# EEZ_AUX_PS_r4B43.net
KiCad netlist of a schematic drawn in EAGLE
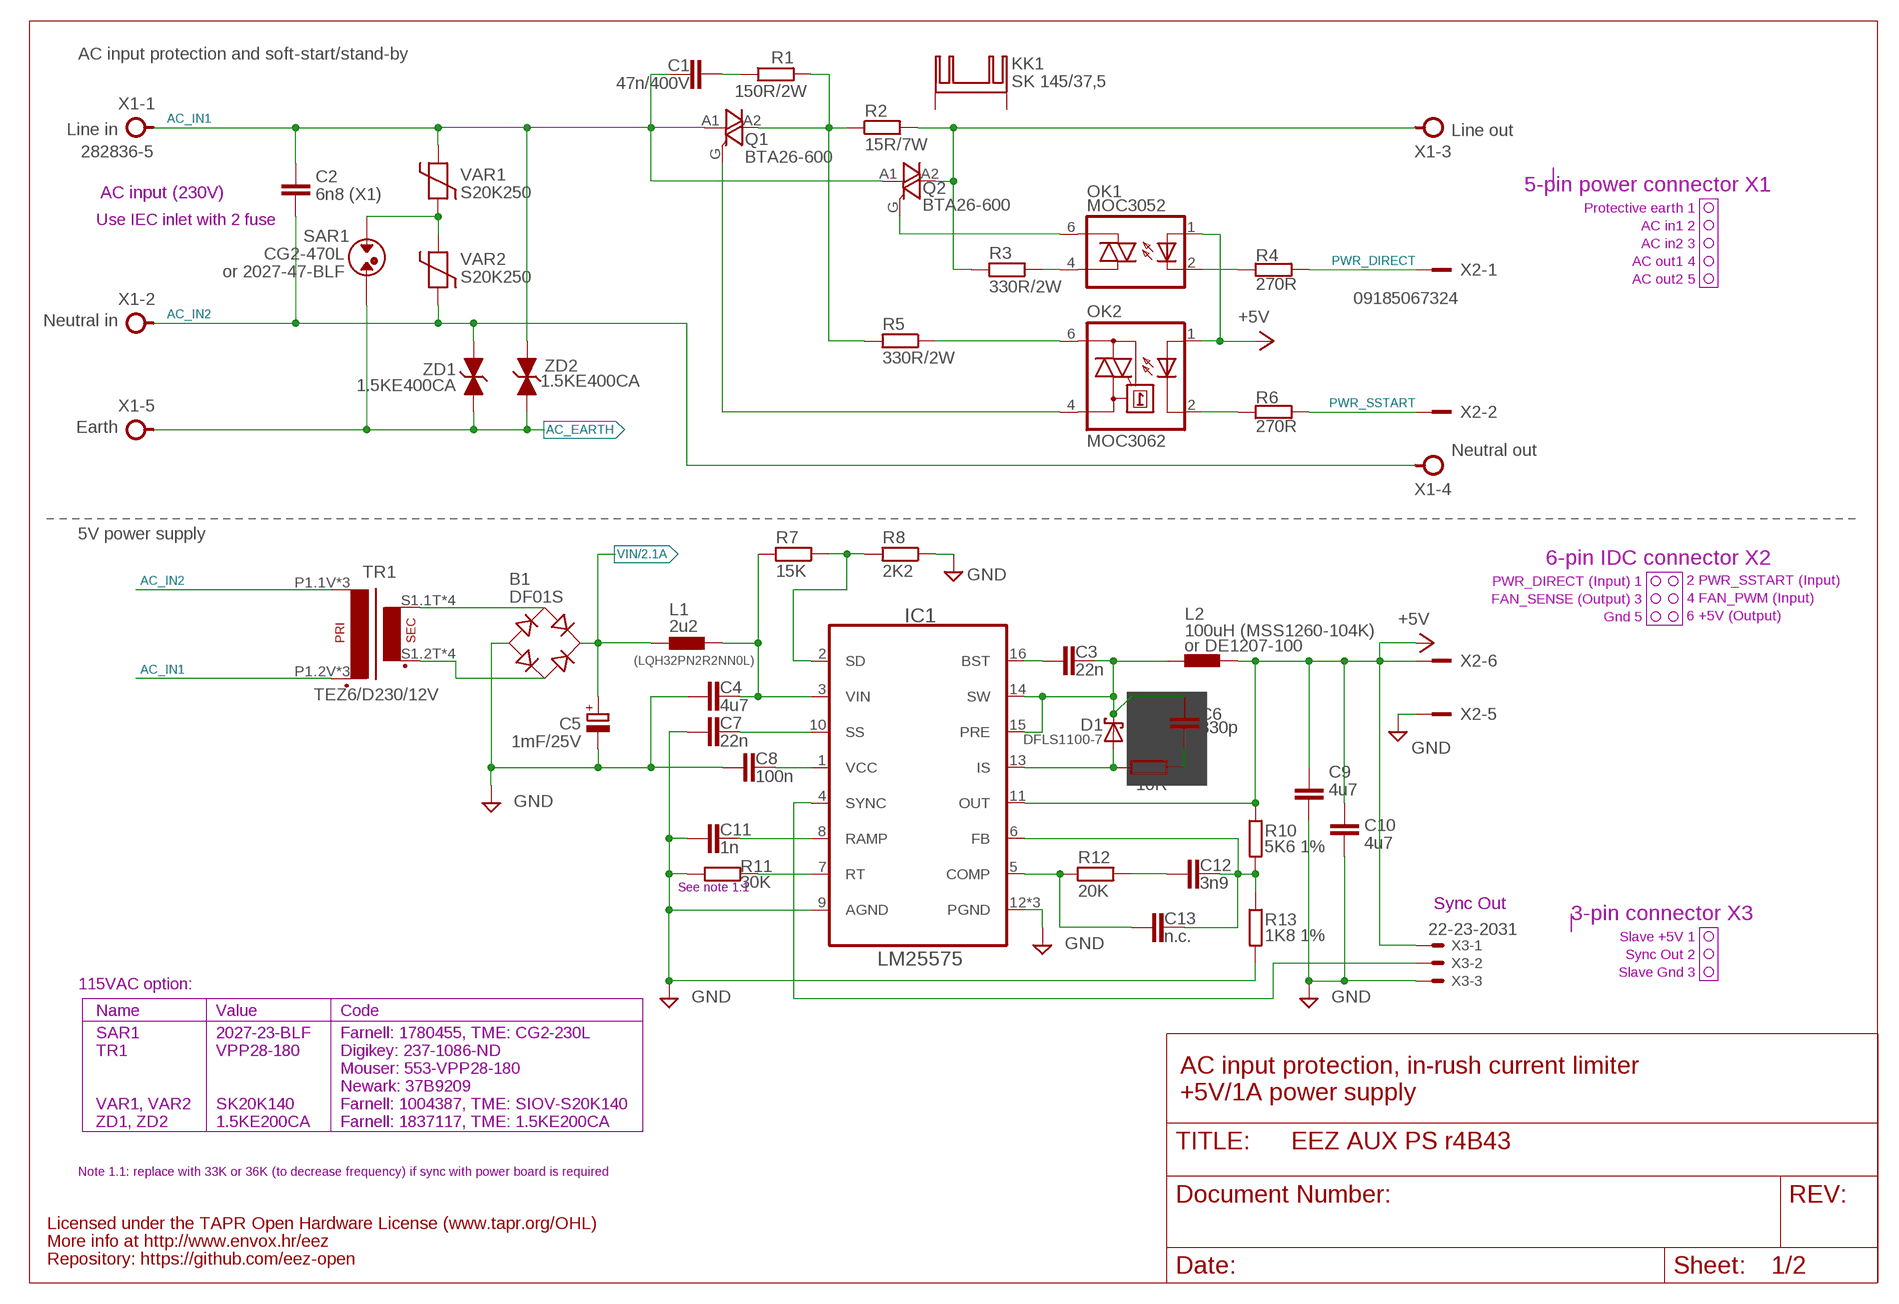
[diagram p0: schematic, sheet 1]
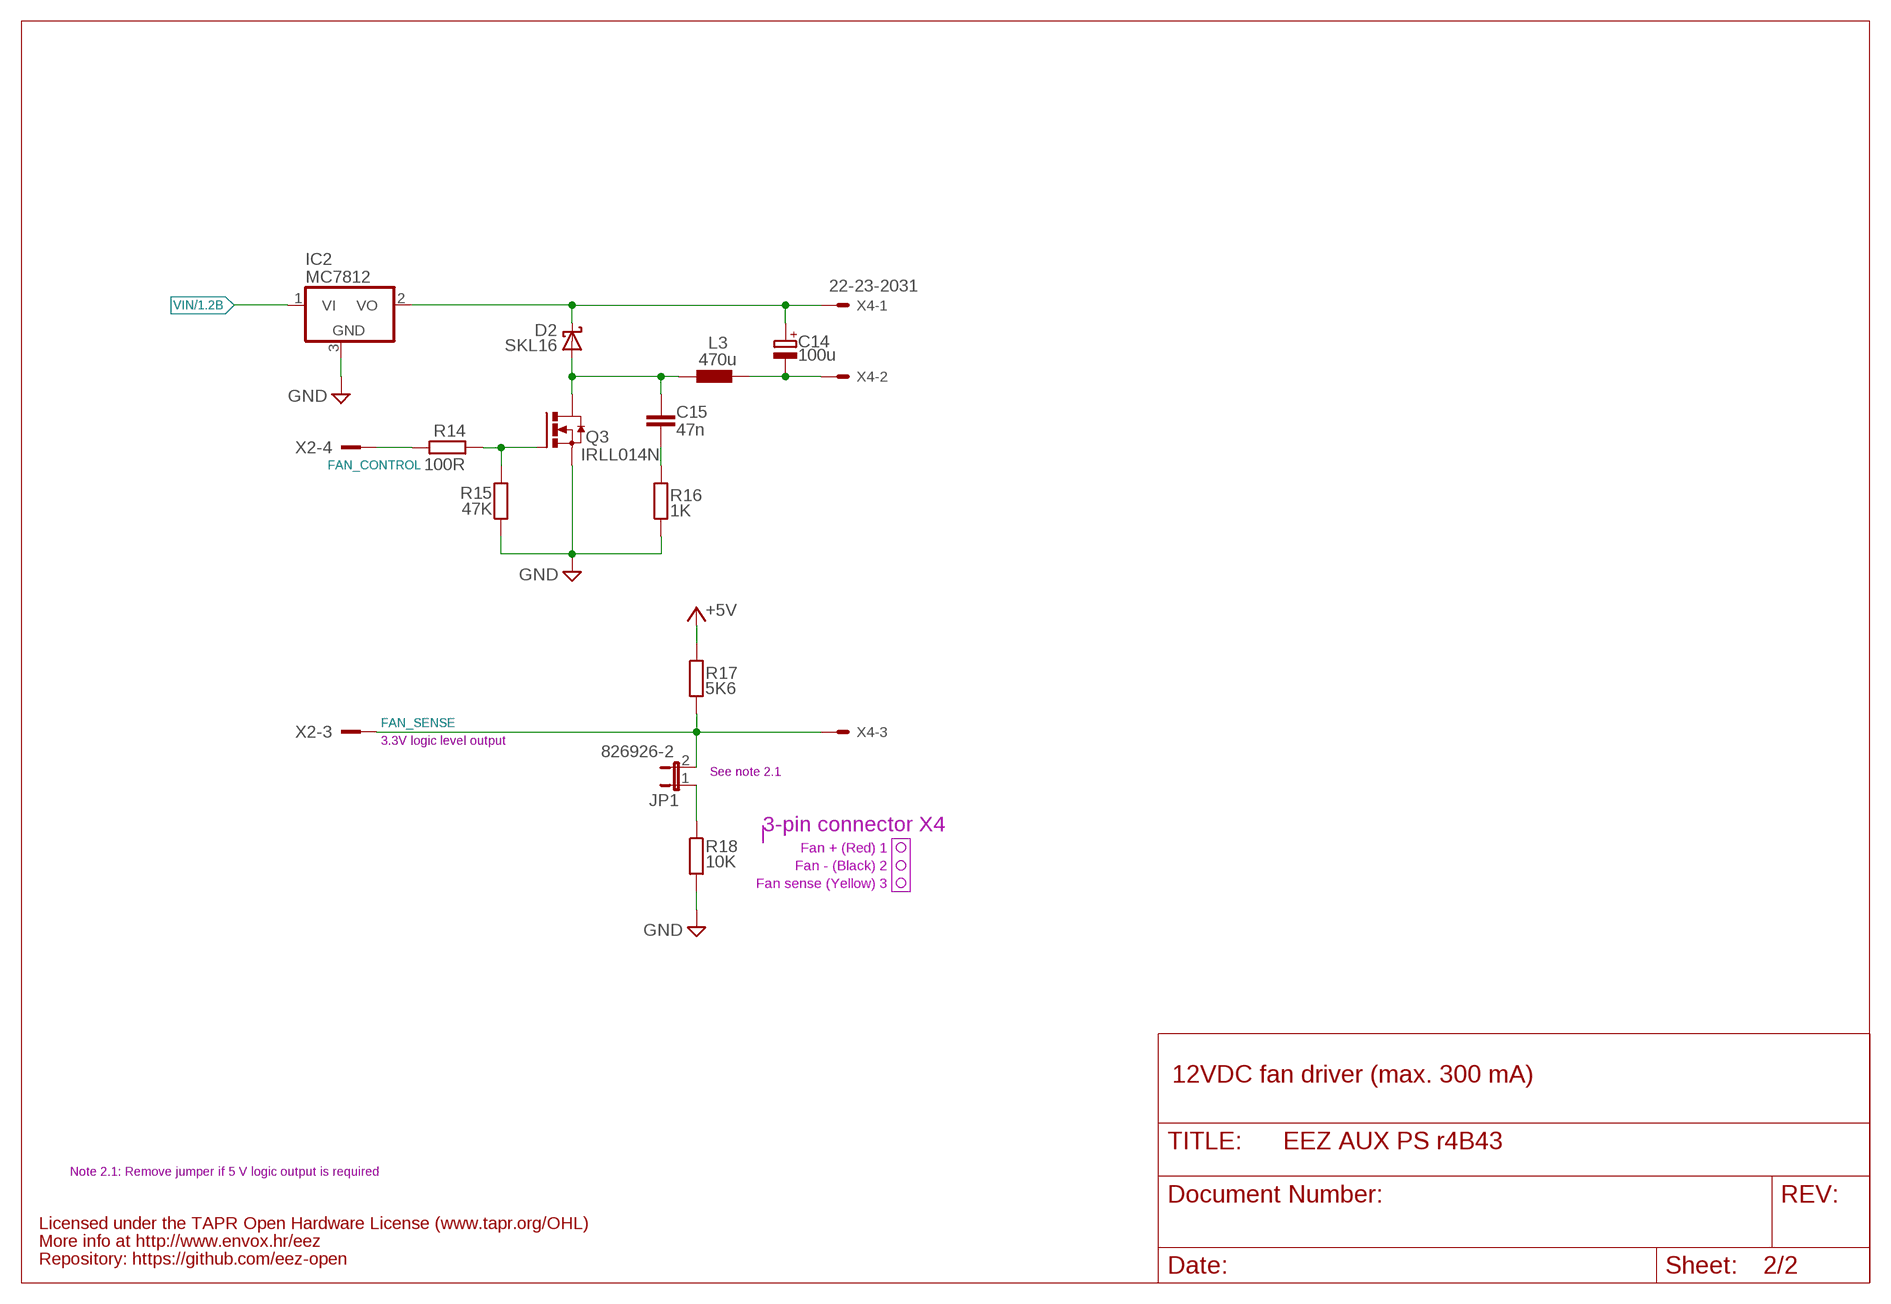
[diagram p1: schematic, sheet 2]

(export (version "E")
  (design (tool "Eeschema 10.0.6"))
  (components
    (comp (ref "B1")
      (value "DF01S")
      (footprint "eagle-import:DFS")
      (libsource (lib "eagle-import") (part "DFS01"))
    )
    (comp (ref "C1")
      (value "47n/400V")
      (footprint "eagle-import:C075-052X106")
      (libsource (lib "eagle-import") (part "C-EU075-052X106"))
    )
    (comp (ref "C2")
      (value "6n8 (X1)")
      (footprint "eagle-import:C102-064X133")
      (libsource (lib "eagle-import") (part "C-EU102-064X133"))
    )
    (comp (ref "C3")
      (value "22n")
      (footprint "eagle-import:C0805")
      (libsource (lib "eagle-import") (part "C-EUC0805"))
    )
    (comp (ref "C4")
      (value "4u7")
      (footprint "eagle-import:C1210")
      (libsource (lib "eagle-import") (part "C-EUC1210"))
    )
    (comp (ref "C5")
      (value "1mF/25V")
      (footprint "eagle-import:ECAP5_10.5")
      (libsource (lib "eagle-import") (part "ECAP5G_10.5MM"))
    )
    (comp (ref "C6")
      (value "330p")
      (footprint "eagle-import:C0805")
      (libsource (lib "eagle-import") (part "C-EUC0805"))
    )
    (comp (ref "C7")
      (value "22n")
      (footprint "eagle-import:C0805")
      (libsource (lib "eagle-import") (part "C-EUC0805"))
    )
    (comp (ref "C8")
      (value "100n")
      (footprint "eagle-import:C0805")
      (libsource (lib "eagle-import") (part "C-EUC0805"))
    )
    (comp (ref "C9")
      (value "4u7")
      (footprint "eagle-import:C1210")
      (libsource (lib "eagle-import") (part "C-EUC1210"))
    )
    (comp (ref "C10")
      (value "4u7")
      (footprint "eagle-import:C1210")
      (libsource (lib "eagle-import") (part "C-EUC1210"))
    )
    (comp (ref "C11")
      (value "1n")
      (footprint "eagle-import:C0805")
      (libsource (lib "eagle-import") (part "C-EUC0805"))
    )
    (comp (ref "C12")
      (value "3n9")
      (footprint "eagle-import:C0805")
      (libsource (lib "eagle-import") (part "C-EUC0805"))
    )
    (comp (ref "C13")
      (value "n.c.")
      (footprint "eagle-import:C0805")
      (libsource (lib "eagle-import") (part "C-EUC0805"))
    )
    (comp (ref "D1")
      (value "DFLS1100-7")
      (footprint "eagle-import:SOD123")
      (libsource (lib "eagle-import") (part "SCHOTTKYSOD123"))
    )
    (comp (ref "IC1")
      (value "LM25575")
      (footprint "eagle-import:SOP65P640X110-17N_HOLE")
      (libsource (lib "eagle-import") (part "LM(2)5575"))
    )
    (comp (ref "KK1")
      (value "SK 145/37,5")
      (footprint "eagle-import:SK145")
      (libsource (lib "eagle-import") (part "SK145"))
    )
    (comp (ref "L1")
      (value "2u2")
      (footprint "eagle-import:L1210")
      (libsource (lib "eagle-import") (part "L1210"))
    )
    (comp (ref "L2")
      (value "100uH (MSS1260-104K)")
      (footprint "eagle-import:MSS1278")
      (libsource (lib "eagle-import") (part "COILCRAFT_MSS1278"))
    )
    (comp (ref "OK1")
      (value "MOC3052")
      (footprint "eagle-import:DIL6-SMD")
      (libsource (lib "eagle-import") (part "MOC305X"))
    )
    (comp (ref "OK2")
      (value "MOC3062")
      (footprint "eagle-import:DIL6-SMD")
      (fields
        (field (name "MF") "FAIRCHILD SEMICONDUCTOR")
        (field (name "MPN") "MOC3033S-M")
        (field (name "MF_1") "FAIRCHILD SEMICONDUCTOR")
        (field (name "MPN_1") "MOC3033S-M")
        (field (name "OC_FARNELL") "unknown")
        (field (name "OC_NEWARK") "05C2878")
      )
      (libsource (lib "eagle-import") (part "MOC30S33"))
    )
    (comp (ref "Q1")
      (value "BTA26-600")
      (footprint "eagle-import:TOP3S-1")
      (libsource (lib "eagle-import") (part "BTA26-V"))
    )
    (comp (ref "Q2")
      (value "BTA26-600")
      (footprint "eagle-import:TOP3S-1")
      (libsource (lib "eagle-import") (part "BTA26-V"))
    )
    (comp (ref "R1")
      (value "150R/2W")
      (footprint "eagle-import:R2512")
      (libsource (lib "eagle-import") (part "R-EU_R2512"))
    )
    (comp (ref "R2")
      (value "15R/7W")
      (footprint "eagle-import:R_0913")
      (libsource (lib "eagle-import") (part "R_EU7W"))
    )
    (comp (ref "R3")
      (value "330R/2W")
      (footprint "eagle-import:R2512")
      (libsource (lib "eagle-import") (part "R-EU_R2512"))
    )
    (comp (ref "R4")
      (value "270R")
      (footprint "eagle-import:R0805")
      (libsource (lib "eagle-import") (part "R-EU_R0805"))
    )
    (comp (ref "R5")
      (value "330R/2W")
      (footprint "eagle-import:R2512")
      (libsource (lib "eagle-import") (part "R-EU_R2512"))
    )
    (comp (ref "R6")
      (value "270R")
      (footprint "eagle-import:R0805")
      (libsource (lib "eagle-import") (part "R-EU_R0805"))
    )
    (comp (ref "R7")
      (value "15K")
      (footprint "eagle-import:R0805")
      (libsource (lib "eagle-import") (part "R-EU_R0805"))
    )
    (comp (ref "R8")
      (value "2K2")
      (footprint "eagle-import:R0805")
      (libsource (lib "eagle-import") (part "R-EU_R0805"))
    )
    (comp (ref "R9")
      (value "10R")
      (footprint "eagle-import:R1206")
      (libsource (lib "eagle-import") (part "R-EU_R1206"))
    )
    (comp (ref "R10")
      (value "5K6 1%")
      (footprint "eagle-import:R0805")
      (libsource (lib "eagle-import") (part "R-EU_R0805"))
    )
    (comp (ref "R11")
      (value "30K")
      (footprint "eagle-import:R0805")
      (libsource (lib "eagle-import") (part "R-EU_R0805"))
    )
    (comp (ref "R12")
      (value "20K")
      (footprint "eagle-import:R0805")
      (libsource (lib "eagle-import") (part "R-EU_R0805"))
    )
    (comp (ref "R13")
      (value "1K8 1%")
      (footprint "eagle-import:R0805")
      (libsource (lib "eagle-import") (part "R-EU_R0805"))
    )
    (comp (ref "SAR1")
      (value "CG2-470L")
      (footprint "eagle-import:SAR")
      (libsource (lib "eagle-import") (part "SAR"))
    )
    (comp (ref "TR1")
      (value "TEZ6/D230/12V")
      (footprint "eagle-import:PCB_TRAFO6VA_TEZ+VPP")
      (libsource (lib "eagle-import") (part "PCB_TRAFO6VA_TEZ+VPP"))
    )
    (comp (ref "VAR1")
      (value "S20K250")
      (footprint "eagle-import:VARISTOR")
      (libsource (lib "eagle-import") (part "VARISTOR"))
    )
    (comp (ref "VAR2")
      (value "S20K250")
      (footprint "eagle-import:VARISTOR")
      (libsource (lib "eagle-import") (part "VARISTOR"))
    )
    (comp (ref "X1")
      (value "282836-5")
      (footprint "eagle-import:TBLOCK5.0_5")
      (libsource (lib "eagle-import") (part "TBLOCK5.0_5A"))
    )
    (comp (ref "X2")
      (value "09185067324")
      (footprint "eagle-import:IDC-6PIN")
      (libsource (lib "eagle-import") (part "IDC-6PIN"))
    )
    (comp (ref "X3")
      (value "22-23-2031")
      (footprint "eagle-import:22-23-2031")
      (fields (field (name "MF") "MOLEX"))
      (libsource (lib "eagle-import") (part "22-23-2031"))
    )
    (comp (ref "ZD1")
      (value "1.5KE400CA")
      (footprint "eagle-import:DO201-BIDIR")
      (libsource (lib "eagle-import") (part "1.5KE-BIDIR"))
    )
    (comp (ref "ZD2")
      (value "1.5KE400CA")
      (footprint "eagle-import:DO201-BIDIR")
      (libsource (lib "eagle-import") (part "1.5KE-BIDIR"))
    )
    (comp (ref "C14")
      (value "100u")
      (footprint "eagle-import:CAPAE660X610N")
      (libsource (lib "eagle-import") (part "ECAPPANASONIC_H"))
    )
    (comp (ref "C15")
      (value "47n")
      (footprint "eagle-import:C0805")
      (libsource (lib "eagle-import") (part "C-EUC0805"))
    )
    (comp (ref "D2")
      (value "SKL16")
      (footprint "eagle-import:SOD123")
      (libsource (lib "eagle-import") (part "SCHOTTKYSOD123"))
    )
    (comp (ref "IC2")
      (value "MC7812")
      (footprint "eagle-import:TO252")
      (libsource (lib "eagle-import") (part "MC78XX"))
    )
    (comp (ref "JP1")
      (value "826926-2")
      (footprint "eagle-import:JP1")
      (libsource (lib "eagle-import") (part "JP1E"))
    )
    (comp (ref "L3")
      (value "470u")
      (footprint "eagle-import:DE0704")
      (libsource (lib "eagle-import") (part "DE0704"))
    )
    (comp (ref "Q3")
      (value "IRLL014N")
      (footprint "eagle-import:SOT223")
      (libsource (lib "eagle-import") (part "N-HEXFET-2D_?-SOT232IRLL014N"))
    )
    (comp (ref "R14")
      (value "100R")
      (footprint "eagle-import:R0805")
      (libsource (lib "eagle-import") (part "R-EU_R0805"))
    )
    (comp (ref "R15")
      (value "47K")
      (footprint "eagle-import:R0805")
      (libsource (lib "eagle-import") (part "R-EU_R0805"))
    )
    (comp (ref "R16")
      (value "1K")
      (footprint "eagle-import:R0805")
      (libsource (lib "eagle-import") (part "R-EU_R0805"))
    )
    (comp (ref "R17")
      (value "5K6")
      (footprint "eagle-import:R0805")
      (libsource (lib "eagle-import") (part "R-EU_R0805"))
    )
    (comp (ref "R18")
      (value "10K")
      (footprint "eagle-import:R0805")
      (libsource (lib "eagle-import") (part "R-EU_R0805"))
    )
    (comp (ref "X4")
      (value "22-23-2031")
      (footprint "eagle-import:22-23-2031")
      (fields (field (name "MF") "MOLEX"))
      (libsource (lib "eagle-import") (part "22-23-2031"))
    )
  )
  (nets
    (net (code "1") (name "+5V") (class "Default")
      (node (ref "C10") (pin "1") (pinfunction "1_1") (pintype "passive"))
      (node (ref "C9") (pin "1") (pinfunction "1_1") (pintype "passive"))
      (node (ref "IC1") (pin "11") (pinfunction "OUT_11") (pintype "output"))
      (node (ref "L2") (pin "2") (pinfunction "2_2") (pintype "passive"))
      (node (ref "OK1") (pin "1") (pinfunction "A_1") (pintype "passive"))
      (node (ref "OK2") (pin "1") (pinfunction "A_1") (pintype "passive"))
      (node (ref "R10") (pin "1") (pinfunction "1_1") (pintype "passive"))
      (node (ref "R17") (pin "1") (pinfunction "1_1") (pintype "passive"))
      (node (ref "X2") (pin "6") (pinfunction "1_6") (pintype "passive"))
      (node (ref "X3") (pin "1") (pinfunction "S_1") (pintype "passive"))
    )
    (net (code "2") (name "AC_EARTH") (class "Default")
      (node (ref "SAR1") (pin "P$2") (pinfunction "P$2_P$2") (pintype "bidirectional"))
      (node (ref "X1") (pin "5") (pinfunction "1_5") (pintype "bidirectional"))
      (node (ref "ZD1") (pin "C") (pinfunction "1_C") (pintype "passive"))
      (node (ref "ZD2") (pin "C") (pinfunction "1_C") (pintype "passive"))
    )
    (net (code "3") (name "AC_IN1") (class "Default")
      (node (ref "C1") (pin "2") (pinfunction "2_2") (pintype "passive"))
      (node (ref "C2") (pin "1") (pinfunction "1_1") (pintype "passive"))
      (node (ref "Q1") (pin "A1") (pinfunction "A1_A1") (pintype "passive"))
      (node (ref "Q2") (pin "A1") (pinfunction "A1_A1") (pintype "passive"))
      (node (ref "TR1") (pin "P1.2V") (pinfunction "P2_P1.2V") (pintype "passive"))
      (node (ref "TR1") (pin "P2.2V") (pinfunction "P2_P2.2V") (pintype "passive"))
      (node (ref "TR1") (pin "P2_TEZ") (pinfunction "P2_P2_TEZ") (pintype "passive"))
      (node (ref "VAR1") (pin "P$2") (pinfunction "P$2_P$2") (pintype "bidirectional"))
      (node (ref "X1") (pin "1") (pinfunction "1_1") (pintype "bidirectional"))
      (node (ref "ZD2") (pin "A") (pinfunction "2_A") (pintype "passive"))
    )
    (net (code "4") (name "AC_IN2") (class "Default")
      (node (ref "C2") (pin "2") (pinfunction "2_2") (pintype "passive"))
      (node (ref "TR1") (pin "P1.1V") (pinfunction "P1_P1.1V") (pintype "passive"))
      (node (ref "TR1") (pin "P1_TEZ") (pinfunction "P1_P1_TEZ") (pintype "passive"))
      (node (ref "TR1") (pin "P2.1V") (pinfunction "P1_P2.1V") (pintype "passive"))
      (node (ref "VAR2") (pin "P$1") (pinfunction "P$1_P$1") (pintype "bidirectional"))
      (node (ref "X1") (pin "2") (pinfunction "1_2") (pintype "bidirectional"))
      (node (ref "X1") (pin "4") (pinfunction "1_4") (pintype "bidirectional"))
      (node (ref "ZD1") (pin "A") (pinfunction "2_A") (pintype "passive"))
    )
    (net (code "5") (name "FAN_CONTROL") (class "Default")
      (node (ref "R14") (pin "2") (pinfunction "2_2") (pintype "passive"))
      (node (ref "X2") (pin "4") (pinfunction "1_4") (pintype "passive"))
    )
    (net (code "6") (name "FAN_SENSE") (class "Default")
      (node (ref "JP1") (pin "2") (pinfunction "2_2") (pintype "passive"))
      (node (ref "R17") (pin "2") (pinfunction "2_2") (pintype "passive"))
      (node (ref "X2") (pin "3") (pinfunction "1_3") (pintype "passive"))
      (node (ref "X4") (pin "3") (pinfunction "S_3") (pintype "passive"))
    )
    (net (code "7") (name "GND") (class "Default")
      (node (ref "B1") (pin "-") (pinfunction "-_-") (pintype "passive"))
      (node (ref "C10") (pin "2") (pinfunction "2_2") (pintype "passive"))
      (node (ref "C11") (pin "1") (pinfunction "1_1") (pintype "passive"))
      (node (ref "C4") (pin "2") (pinfunction "2_2") (pintype "passive"))
      (node (ref "C5") (pin "-") (pinfunction "-_-") (pintype "passive"))
      (node (ref "C7") (pin "2") (pinfunction "2_2") (pintype "passive"))
      (node (ref "C8") (pin "1") (pinfunction "1_1") (pintype "passive"))
      (node (ref "C9") (pin "2") (pinfunction "2_2") (pintype "passive"))
      (node (ref "IC1") (pin "12") (pinfunction "PGND_12") (pintype "passive"))
      (node (ref "IC1") (pin "9") (pinfunction "AGND_9") (pintype "passive"))
      (node (ref "IC1") (pin "TP") (pinfunction "PGND_TP") (pintype "passive"))
      (node (ref "IC1") (pin "TP2") (pinfunction "PGND_TP2") (pintype "passive"))
      (node (ref "IC2") (pin "3") (pinfunction "GND_3") (pintype "passive"))
      (node (ref "Q3") (pin "3") (pinfunction "S_3") (pintype "passive"))
      (node (ref "R11") (pin "2") (pinfunction "2_2") (pintype "passive"))
      (node (ref "R13") (pin "2") (pinfunction "2_2") (pintype "passive"))
      (node (ref "R15") (pin "1") (pinfunction "1_1") (pintype "passive"))
      (node (ref "R16") (pin "1") (pinfunction "1_1") (pintype "passive"))
      (node (ref "R18") (pin "2") (pinfunction "2_2") (pintype "passive"))
      (node (ref "R8") (pin "1") (pinfunction "1_1") (pintype "passive"))
      (node (ref "X2") (pin "5") (pinfunction "1_5") (pintype "passive"))
      (node (ref "X3") (pin "3") (pinfunction "S_3") (pintype "passive"))
    )
    (net (code "8") (name "Net-(B1-PadAC1)") (class "Default")
      (node (ref "B1") (pin "AC1") (pinfunction "AC1_AC1") (pintype "passive"))
      (node (ref "TR1") (pin "S1.1T") (pinfunction "S1_S1.1T") (pintype "passive"))
      (node (ref "TR1") (pin "S1.1V") (pinfunction "S1_S1.1V") (pintype "passive"))
      (node (ref "TR1") (pin "S2.1T") (pinfunction "S1_S2.1T") (pintype "passive"))
      (node (ref "TR1") (pin "S2.1V") (pinfunction "S1_S2.1V") (pintype "passive"))
    )
    (net (code "9") (name "Net-(B1-PadAC2)") (class "Default")
      (node (ref "B1") (pin "AC2") (pinfunction "AC2_AC2") (pintype "passive"))
      (node (ref "TR1") (pin "S1.2T") (pinfunction "S2_S1.2T") (pintype "passive"))
      (node (ref "TR1") (pin "S1.2V") (pinfunction "S2_S1.2V") (pintype "passive"))
      (node (ref "TR1") (pin "S2.2T") (pinfunction "S2_S2.2T") (pintype "passive"))
      (node (ref "TR1") (pin "S2.2V") (pinfunction "S2_S2.2V") (pintype "passive"))
    )
    (net (code "10") (name "Net-(C1-Pad1)") (class "Default")
      (node (ref "C1") (pin "1") (pinfunction "1_1") (pintype "passive"))
      (node (ref "R1") (pin "1") (pinfunction "1_1") (pintype "passive"))
    )
    (net (code "11") (name "Net-(C6-Pad2)") (class "Default")
      (node (ref "C6") (pin "2") (pinfunction "2_2") (pintype "passive"))
      (node (ref "R9") (pin "2") (pinfunction "2_2") (pintype "passive"))
    )
    (net (code "12") (name "Net-(C12-Pad2)") (class "Default")
      (node (ref "C12") (pin "2") (pinfunction "2_2") (pintype "passive"))
      (node (ref "R12") (pin "2") (pinfunction "2_2") (pintype "passive"))
    )
    (net (code "13") (name "Net-(C14-+)") (class "Default")
      (node (ref "C14") (pin "1") (pinfunction "+_1") (pintype "passive"))
      (node (ref "D2") (pin "C") (pinfunction "C_C") (pintype "passive"))
      (node (ref "IC2") (pin "2") (pinfunction "VO_2") (pintype "passive"))
      (node (ref "X4") (pin "1") (pinfunction "S_1") (pintype "passive"))
    )
    (net (code "14") (name "Net-(C14--)") (class "Default")
      (node (ref "C14") (pin "2") (pinfunction "-_2") (pintype "passive"))
      (node (ref "L3") (pin "1") (pinfunction "1_1") (pintype "passive"))
      (node (ref "X4") (pin "2") (pinfunction "S_2") (pintype "passive"))
    )
    (net (code "15") (name "Net-(C15-Pad1)") (class "Default")
      (node (ref "C15") (pin "1") (pinfunction "1_1") (pintype "passive"))
      (node (ref "R16") (pin "2") (pinfunction "2_2") (pintype "passive"))
    )
    (net (code "16") (name "Net-(C15-Pad2)") (class "Default")
      (node (ref "C15") (pin "2") (pinfunction "2_2") (pintype "passive"))
      (node (ref "D2") (pin "A") (pinfunction "A_A") (pintype "passive"))
      (node (ref "L3") (pin "2") (pinfunction "2_2") (pintype "passive"))
      (node (ref "Q3") (pin "2") (pinfunction "D_2") (pintype "passive"))
      (node (ref "Q3") (pin "4") (pinfunction "D_4") (pintype "passive"))
    )
    (net (code "17") (name "Net-(IC1-BST)") (class "Default")
      (node (ref "C3") (pin "2") (pinfunction "2_2") (pintype "passive"))
      (node (ref "IC1") (pin "16") (pinfunction "BST_16") (pintype "input"))
    )
    (net (code "18") (name "Net-(IC1-COMP)") (class "Default")
      (node (ref "C13") (pin "2") (pinfunction "2_2") (pintype "passive"))
      (node (ref "IC1") (pin "5") (pinfunction "COMP_5") (pintype "input"))
      (node (ref "R12") (pin "1") (pinfunction "1_1") (pintype "passive"))
    )
    (net (code "19") (name "Net-(IC1-FB)") (class "Default")
      (node (ref "C12") (pin "1") (pinfunction "1_1") (pintype "passive"))
      (node (ref "C13") (pin "1") (pinfunction "1_1") (pintype "passive"))
      (node (ref "IC1") (pin "6") (pinfunction "FB_6") (pintype "input"))
      (node (ref "R10") (pin "2") (pinfunction "2_2") (pintype "passive"))
      (node (ref "R13") (pin "1") (pinfunction "1_1") (pintype "passive"))
    )
    (net (code "20") (name "Net-(IC1-IS)") (class "Default")
      (node (ref "D1") (pin "A") (pinfunction "A_A") (pintype "passive"))
      (node (ref "IC1") (pin "13") (pinfunction "IS_13") (pintype "input"))
      (node (ref "R9") (pin "1") (pinfunction "1_1") (pintype "passive"))
    )
    (net (code "21") (name "Net-(IC1-PRE)") (class "Default")
      (node (ref "C3") (pin "1") (pinfunction "1_1") (pintype "passive"))
      (node (ref "C6") (pin "1") (pinfunction "1_1") (pintype "passive"))
      (node (ref "D1") (pin "C") (pinfunction "C_C") (pintype "passive"))
      (node (ref "IC1") (pin "14") (pinfunction "SW_14") (pintype "output"))
      (node (ref "IC1") (pin "15") (pinfunction "PRE_15") (pintype "input"))
      (node (ref "L2") (pin "1") (pinfunction "1_1") (pintype "passive"))
    )
    (net (code "22") (name "Net-(IC1-RAMP)") (class "Default")
      (node (ref "C11") (pin "2") (pinfunction "2_2") (pintype "passive"))
      (node (ref "IC1") (pin "8") (pinfunction "RAMP_8") (pintype "input"))
    )
    (net (code "23") (name "Net-(IC1-RT)") (class "Default")
      (node (ref "IC1") (pin "7") (pinfunction "RT_7") (pintype "input"))
      (node (ref "R11") (pin "1") (pinfunction "1_1") (pintype "passive"))
    )
    (net (code "24") (name "Net-(IC1-SD)") (class "Default")
      (node (ref "IC1") (pin "2") (pinfunction "SD_2") (pintype "input"))
      (node (ref "R7") (pin "1") (pinfunction "1_1") (pintype "passive"))
      (node (ref "R8") (pin "2") (pinfunction "2_2") (pintype "passive"))
    )
    (net (code "25") (name "Net-(IC1-SS)") (class "Default")
      (node (ref "C7") (pin "1") (pinfunction "1_1") (pintype "passive"))
      (node (ref "IC1") (pin "10") (pinfunction "SS_10") (pintype "input"))
    )
    (net (code "26") (name "Net-(IC1-SYNC)") (class "Default")
      (node (ref "IC1") (pin "4") (pinfunction "SYNC_4") (pintype "input"))
      (node (ref "X3") (pin "2") (pinfunction "S_2") (pintype "passive"))
    )
    (net (code "27") (name "Net-(IC1-VCC)") (class "Default")
      (node (ref "C8") (pin "2") (pinfunction "2_2") (pintype "passive"))
      (node (ref "IC1") (pin "1") (pinfunction "VCC_1") (pintype "power_in"))
    )
    (net (code "28") (name "Net-(IC1-VIN)") (class "Default")
      (node (ref "C4") (pin "1") (pinfunction "1_1") (pintype "passive"))
      (node (ref "IC1") (pin "3") (pinfunction "VIN_3") (pintype "input"))
      (node (ref "L1") (pin "2") (pinfunction "2_2") (pintype "passive"))
      (node (ref "R7") (pin "2") (pinfunction "2_2") (pintype "passive"))
    )
    (net (code "29") (name "Net-(JP1-Pad1)") (class "Default")
      (node (ref "JP1") (pin "1") (pinfunction "1_1") (pintype "passive"))
      (node (ref "R18") (pin "1") (pinfunction "1_1") (pintype "passive"))
    )
    (net (code "30") (name "Net-(OK1-A1)") (class "Default")
      (node (ref "OK1") (pin "4") (pinfunction "A1_4") (pintype "passive"))
      (node (ref "R3") (pin "1") (pinfunction "1_1") (pintype "passive"))
    )
    (net (code "31") (name "Net-(OK1-A2)") (class "Default")
      (node (ref "OK1") (pin "6") (pinfunction "A2_6") (pintype "passive"))
      (node (ref "Q2") (pin "G") (pinfunction "G_G") (pintype "passive"))
    )
    (net (code "32") (name "Net-(OK1-C)") (class "Default")
      (node (ref "OK1") (pin "2") (pinfunction "C_2") (pintype "passive"))
      (node (ref "R4") (pin "1") (pinfunction "1_1") (pintype "passive"))
    )
    (net (code "33") (name "Net-(OK2-A1)") (class "Default")
      (node (ref "OK2") (pin "4") (pinfunction "A1_4") (pintype "passive"))
      (node (ref "Q1") (pin "G") (pinfunction "G_G") (pintype "passive"))
    )
    (net (code "34") (name "Net-(OK2-A2)") (class "Default")
      (node (ref "OK2") (pin "6") (pinfunction "A2_6") (pintype "passive"))
      (node (ref "R5") (pin "1") (pinfunction "1_1") (pintype "passive"))
    )
    (net (code "35") (name "Net-(OK2-C)") (class "Default")
      (node (ref "OK2") (pin "2") (pinfunction "C_2") (pintype "passive"))
      (node (ref "R6") (pin "1") (pinfunction "1_1") (pintype "passive"))
    )
    (net (code "36") (name "Net-(Q1-PadA2)") (class "Default")
      (node (ref "Q1") (pin "A2") (pinfunction "A2_A2") (pintype "passive"))
      (node (ref "R1") (pin "2") (pinfunction "2_2") (pintype "passive"))
      (node (ref "R2") (pin "1") (pinfunction "1_1") (pintype "passive"))
      (node (ref "R5") (pin "2") (pinfunction "2_2") (pintype "passive"))
    )
    (net (code "37") (name "Net-(Q3-G)") (class "Default")
      (node (ref "Q3") (pin "1") (pinfunction "G_1") (pintype "passive"))
      (node (ref "R14") (pin "1") (pinfunction "1_1") (pintype "passive"))
      (node (ref "R15") (pin "2") (pinfunction "2_2") (pintype "passive"))
    )
    (net (code "38") (name "Net-(SAR1-PadP$1)") (class "Default")
      (node (ref "SAR1") (pin "P$1") (pinfunction "P$1_P$1") (pintype "bidirectional"))
      (node (ref "VAR1") (pin "P$1") (pinfunction "P$1_P$1") (pintype "bidirectional"))
      (node (ref "VAR2") (pin "P$2") (pinfunction "P$2_P$2") (pintype "bidirectional"))
    )
    (net (code "39") (name "Net-(X1C-1)") (class "Default")
      (node (ref "Q2") (pin "A2") (pinfunction "A2_A2") (pintype "passive"))
      (node (ref "R2") (pin "2") (pinfunction "2_2") (pintype "passive"))
      (node (ref "R3") (pin "2") (pinfunction "2_2") (pintype "passive"))
      (node (ref "X1") (pin "3") (pinfunction "1_3") (pintype "bidirectional"))
    )
    (net (code "40") (name "PWR_DIRECT") (class "Default")
      (node (ref "R4") (pin "2") (pinfunction "2_2") (pintype "passive"))
      (node (ref "X2") (pin "1") (pinfunction "1_1") (pintype "passive"))
    )
    (net (code "41") (name "PWR_SSTART") (class "Default")
      (node (ref "R6") (pin "2") (pinfunction "2_2") (pintype "passive"))
      (node (ref "X2") (pin "2") (pinfunction "1_2") (pintype "passive"))
    )
    (net (code "42") (name "VIN") (class "Default")
      (node (ref "B1") (pin "+") (pinfunction "+_+") (pintype "passive"))
      (node (ref "C5") (pin "+") (pinfunction "+_+") (pintype "passive"))
      (node (ref "IC2") (pin "1") (pinfunction "VI_1") (pintype "input"))
      (node (ref "L1") (pin "1") (pinfunction "1_1") (pintype "passive"))
    )
    (net (code "43") (name "unconnected-(KK1-K-Pad1)") (class "Default")
      (node (ref "KK1") (pin "1") (pinfunction "K_1") (pintype "passive"))
    )
    (net (code "44") (name "unconnected-(KK1-K-Pad2)") (class "Default")
      (node (ref "KK1") (pin "2") (pinfunction "K_2") (pintype "passive"))
    )
  )
)
